# CAS_2.net
KiCad netlist of a schematic drawn in Altium Designer
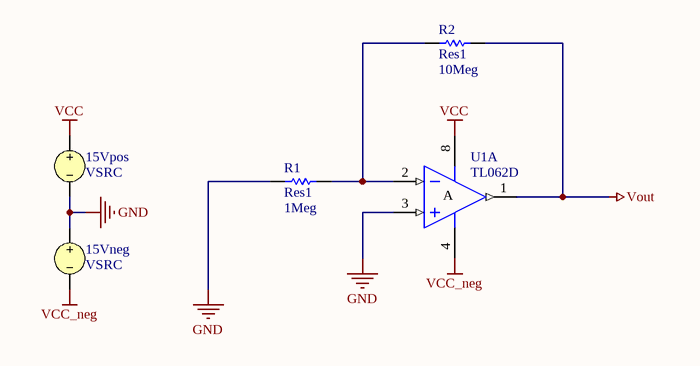
[diagram p0: CAS_2.SchDoc]

(export (version "E")
  (design (tool "Eeschema 10.0.6"))
  (components
    (comp (ref "15Vneg")
      (value "VSRC")
      (description "Voltage Source")
      (fields (field (name "PUBLISHER") "Altium Limited"))
      (libsource (lib "Simulation Generic Components") (part "VSRC"))
    )
    (comp (ref "15Vpos")
      (value "VSRC")
      (description "Voltage Source")
      (fields (field (name "PUBLISHER") "Altium Limited"))
      (libsource (lib "Simulation Generic Components") (part "VSRC"))
    )
    (comp (ref "R1")
      (value "Res1")
      (footprint "AXIAL-0.3")
      (description "Resistor")
      (fields (field (name "ALTIUM_VALUE") "1Meg") (field (name "PUBLISHER") "Altium Limited"))
      (libsource (lib "Miscellaneous Devices") (part "Res1"))
    )
    (comp (ref "R2")
      (value "Res1")
      (footprint "AXIAL-0.3")
      (description "Resistor")
      (fields (field (name "ALTIUM_VALUE") "10Meg") (field (name "PUBLISHER") "Altium Limited"))
      (libsource (lib "Miscellaneous Devices") (part "Res1"))
    )
    (comp (ref "U1")
      (value "TL062D")
      (footprint "D008_L")
      (description "Low-Power JFET-Input Operational Amplifier")
      (fields (field (name "PUBLISHER") "Altium Limited"))
      (libsource (lib "TI Operational Amplifier") (part "TL062D"))
    )
  )
  (nets
    (net (code "1") (name "GND") (class "Default")
      (node (ref "15Vneg") (pin "1") (pinfunction "1_1") (pintype "passive"))
      (node (ref "15Vpos") (pin "2") (pinfunction "2_2") (pintype "passive"))
      (node (ref "R1") (pin "1") (pinfunction "1_1") (pintype "passive"))
      (node (ref "U1") (pin "3") (pinfunction "IN+_3") (pintype "input"))
    )
    (net (code "2") (name "Net-(U1A-IN-)") (class "Default")
      (node (ref "R1") (pin "2") (pinfunction "2_2") (pintype "passive"))
      (node (ref "R2") (pin "1") (pinfunction "1_1") (pintype "passive"))
      (node (ref "U1") (pin "2") (pinfunction "IN-_2") (pintype "input"))
    )
    (net (code "3") (name "VCC") (class "Default")
      (node (ref "15Vpos") (pin "1") (pinfunction "1_1") (pintype "passive"))
      (node (ref "U1") (pin "8") (pinfunction "V+_8") (pintype "power_in"))
    )
    (net (code "4") (name "VCC_neg") (class "Default")
      (node (ref "15Vneg") (pin "2") (pinfunction "2_2") (pintype "passive"))
      (node (ref "U1") (pin "4") (pinfunction "V-_4") (pintype "power_in"))
    )
    (net (code "5") (name "Vout") (class "Default")
      (node (ref "R2") (pin "2") (pinfunction "2_2") (pintype "passive"))
      (node (ref "U1") (pin "1") (pinfunction "OUT_1") (pintype "output"))
    )
  )
)
